# Miscellaneous.net
KiCad netlist of a schematic drawn in Altium Designer
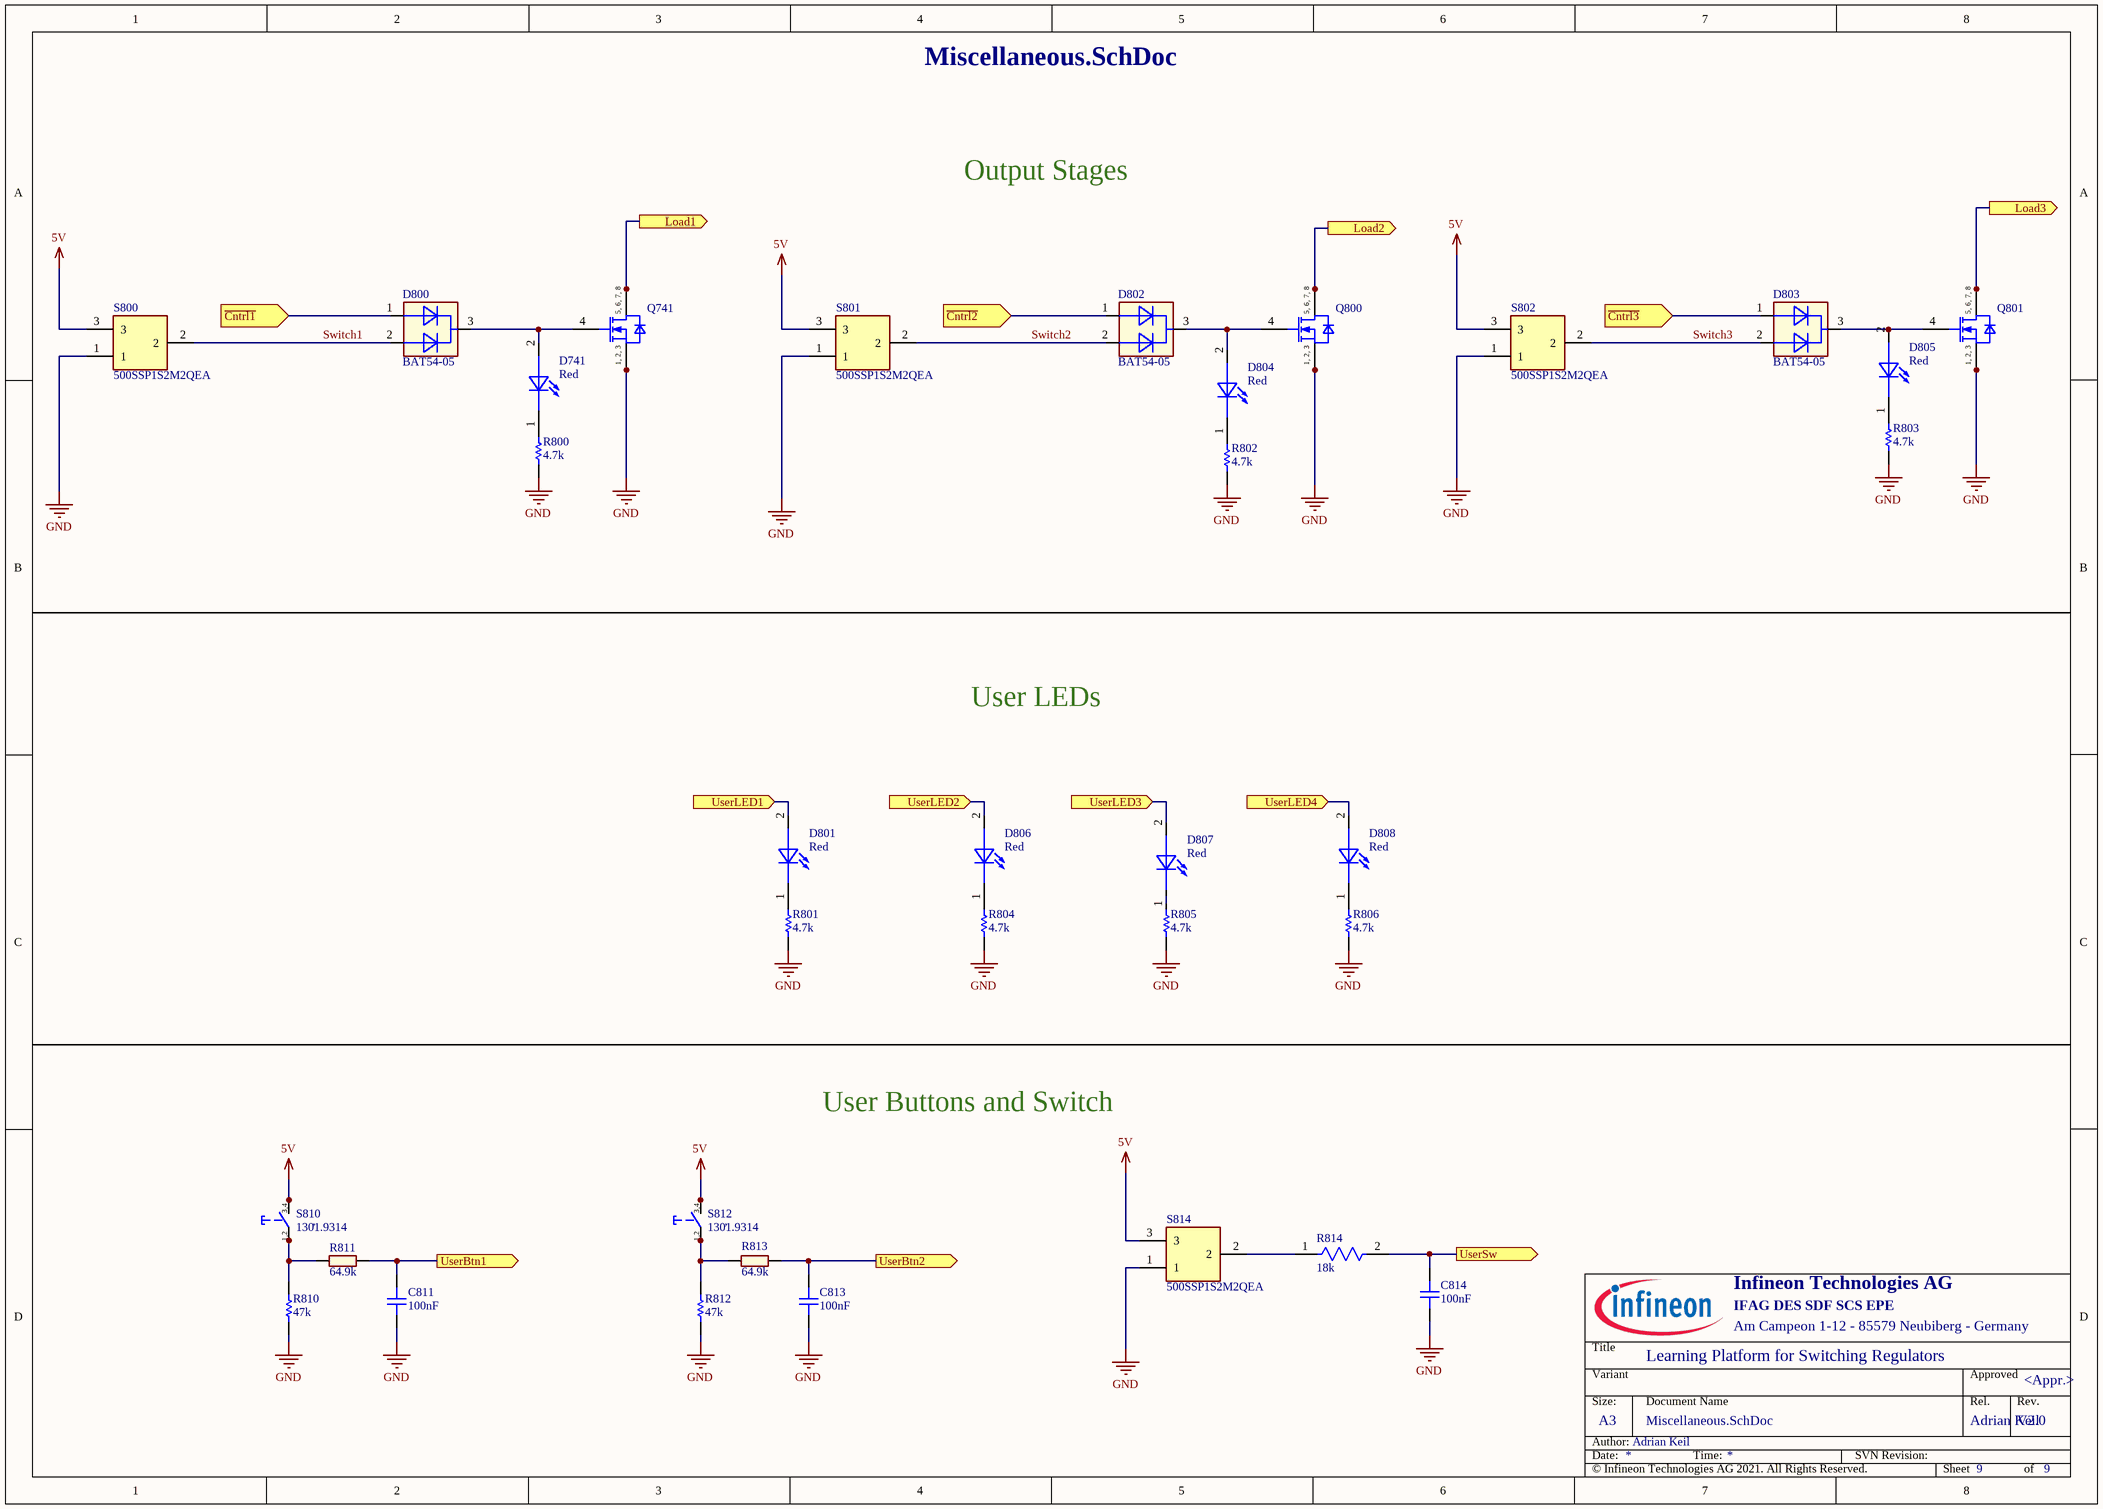
[diagram p0: Miscellaneous.SchDoc]

(export (version "E")
  (design (tool "Eeschema 10.0.6"))
  (components
    (comp (ref "C811")
      (value "100nF")
      (footprint "CAPC3216X125N-0")
      (description "CAP / CERA / 100nF / 50V / 10% / X7R (EIA) / -55°C to 125°C / 1206(3216) / SMD / -")
      (fields (field (name "LEGACY PARTNUMBER") "CAP01005660") (field (name "MANUFACTURER") "MuRata"))
      (libsource (lib "PCBLibraryData") (part "CAP-SGL-STD-02P_00000001"))
    )
    (comp (ref "C813")
      (value "100nF")
      (footprint "CAPC3216X125N-0")
      (description "CAP / CERA / 100nF / 50V / 10% / X7R (EIA) / -55°C to 125°C / 1206(3216) / SMD / -")
      (fields (field (name "LEGACY PARTNUMBER") "CAP01005660") (field (name "MANUFACTURER") "MuRata"))
      (libsource (lib "PCBLibraryData") (part "CAP-SGL-STD-02P_00000001"))
    )
    (comp (ref "C814")
      (value "100nF")
      (footprint "CAPC3216X125N-0")
      (description "CAP / CERA / 100nF / 50V / 10% / X7R (EIA) / -55°C to 125°C / 1206(3216) / SMD / -")
      (fields (field (name "LEGACY PARTNUMBER") "CAP01005660") (field (name "MANUFACTURER") "MuRata"))
      (libsource (lib "PCBLibraryData") (part "CAP-SGL-STD-02P_00000001"))
    )
    (comp (ref "D741")
      (value "Red")
      (footprint "LEDSC160X80X80-2N-1")
      (description "WL-SMCW SMT Mono-color Chip LED Waterclear, Red,630nm")
      (fields (field (name "MANUFACTURER") "Wurth Elektronik"))
      (libsource (lib "PCBLibraryData") (part "d_led_a"))
    )
    (comp (ref "D800")
      (value "BAT54-05")
      (footprint "SOT95P240X110-3N-1-V")
      (description "Silicon Schottky Diode, LS(nH) 1.8, VR 30V")
      (fields
        (field (name "LEGACY PARTNUMBER") "IFX01401370")
        (field (name "MANUFACTURER") "Infineon Technologies")
      )
      (libsource (lib "PCBLibraryData") (part "d_dual_a1a2c3_3p"))
    )
    (comp (ref "D801")
      (value "Red")
      (footprint "LEDSC160X80X80-2N-1")
      (description "WL-SMCW SMT Mono-color Chip LED Waterclear, Red,630nm")
      (fields (field (name "MANUFACTURER") "Wurth Elektronik"))
      (libsource (lib "PCBLibraryData") (part "d_led_a"))
    )
    (comp (ref "D802")
      (value "BAT54-05")
      (footprint "SOT95P240X110-3N-1-V")
      (description "Silicon Schottky Diode, LS(nH) 1.8, VR 30V")
      (fields
        (field (name "LEGACY PARTNUMBER") "IFX01401370")
        (field (name "MANUFACTURER") "Infineon Technologies")
      )
      (libsource (lib "PCBLibraryData") (part "d_dual_a1a2c3_3p"))
    )
    (comp (ref "D803")
      (value "BAT54-05")
      (footprint "SOT95P240X110-3N-1-V")
      (description "Silicon Schottky Diode, LS(nH) 1.8, VR 30V")
      (fields
        (field (name "LEGACY PARTNUMBER") "IFX01401370")
        (field (name "MANUFACTURER") "Infineon Technologies")
      )
      (libsource (lib "PCBLibraryData") (part "d_dual_a1a2c3_3p"))
    )
    (comp (ref "D804")
      (value "Red")
      (footprint "LEDSC160X80X80-2N-1")
      (description "WL-SMCW SMT Mono-color Chip LED Waterclear, Red,630nm")
      (fields (field (name "MANUFACTURER") "Wurth Elektronik"))
      (libsource (lib "PCBLibraryData") (part "d_led_a"))
    )
    (comp (ref "D805")
      (value "Red")
      (footprint "LEDSC160X80X80-2N-1")
      (description "WL-SMCW SMT Mono-color Chip LED Waterclear, Red,630nm")
      (fields (field (name "MANUFACTURER") "Wurth Elektronik"))
      (libsource (lib "PCBLibraryData") (part "d_led_a"))
    )
    (comp (ref "D806")
      (value "Red")
      (footprint "LEDSC160X80X80-2N-1")
      (description "WL-SMCW SMT Mono-color Chip LED Waterclear, Red,630nm")
      (fields (field (name "MANUFACTURER") "Wurth Elektronik"))
      (libsource (lib "PCBLibraryData") (part "d_led_a"))
    )
    (comp (ref "D807")
      (value "Red")
      (footprint "LEDSC160X80X80-2N-1")
      (description "WL-SMCW SMT Mono-color Chip LED Waterclear, Red,630nm")
      (fields (field (name "MANUFACTURER") "Wurth Elektronik"))
      (libsource (lib "PCBLibraryData") (part "d_led_a"))
    )
    (comp (ref "D808")
      (value "Red")
      (footprint "LEDSC160X80X80-2N-1")
      (description "WL-SMCW SMT Mono-color Chip LED Waterclear, Red,630nm")
      (fields (field (name "MANUFACTURER") "Wurth Elektronik"))
      (libsource (lib "PCBLibraryData") (part "d_led_a"))
    )
    (comp (ref "Q741")
      (value "igfet_n_ch_enh_dio_1s2s3s4g5d6d7d8d_8p")
      (footprint "IFX-PG-TDSON-8-6-V")
      (description "OptiMOS Power MOSFET, 30V")
      (fields (field (name "MANUFACTURER") "Infineon Technologies") (field (name "MPN") "BSC0906NSATMA1"))
      (libsource (lib "PCBLibraryData") (part "igfet_n_ch_enh_dio_1s2s3s4g5d6d7d8d_8p"))
    )
    (comp (ref "Q800")
      (value "igfet_n_ch_enh_dio_1s2s3s4g5d6d7d8d_8p")
      (footprint "IFX-PG-TDSON-8-6-V")
      (description "OptiMOS Power MOSFET, 30V")
      (fields (field (name "MANUFACTURER") "Infineon Technologies"))
      (libsource (lib "PCBLibraryData") (part "igfet_n_ch_enh_dio_1s2s3s4g5d6d7d8d_8p"))
    )
    (comp (ref "Q801")
      (value "igfet_n_ch_enh_dio_1s2s3s4g5d6d7d8d_8p")
      (footprint "IFX-PG-TDSON-8-6-V")
      (description "OptiMOS Power MOSFET, 30V")
      (fields (field (name "MANUFACTURER") "Infineon Technologies"))
      (libsource (lib "PCBLibraryData") (part "igfet_n_ch_enh_dio_1s2s3s4g5d6d7d8d_8p"))
    )
    (comp (ref "R800")
      (value "4.7k")
      (footprint "RESC3216X60X45ML15T20")
      (description "Chip Resistor, 4.7 KOhm, +/- 1%, 0.25 W, -55 to 155 degC, 1206 (3216 Metric), RoHS, Tape and Reel")
      (fields (field (name "MANUFACTURER") "Vishay Semiconductor") (field (name "TOLERANCE") "1%"))
      (libsource (lib "Altium Content Vault") (part "RES-2"))
    )
    (comp (ref "R801")
      (value "4.7k")
      (footprint "RESC3216X60X45ML15T20")
      (description "Chip Resistor, 4.7 KOhm, +/- 1%, 0.25 W, -55 to 155 degC, 1206 (3216 Metric), RoHS, Tape and Reel")
      (fields (field (name "MANUFACTURER") "Vishay Semiconductor") (field (name "TOLERANCE") "1%"))
      (libsource (lib "Altium Content Vault") (part "RES-2"))
    )
    (comp (ref "R802")
      (value "4.7k")
      (footprint "RESC3216X60X45ML15T20")
      (description "Chip Resistor, 4.7 KOhm, +/- 1%, 0.25 W, -55 to 155 degC, 1206 (3216 Metric), RoHS, Tape and Reel")
      (fields (field (name "MANUFACTURER") "Vishay Semiconductor") (field (name "TOLERANCE") "1%"))
      (libsource (lib "Altium Content Vault") (part "RES-2"))
    )
    (comp (ref "R803")
      (value "4.7k")
      (footprint "RESC3216X60X45ML15T20")
      (description "Chip Resistor, 4.7 KOhm, +/- 1%, 0.25 W, -55 to 155 degC, 1206 (3216 Metric), RoHS, Tape and Reel")
      (fields (field (name "MANUFACTURER") "Vishay Semiconductor") (field (name "TOLERANCE") "1%"))
      (libsource (lib "Altium Content Vault") (part "RES-2"))
    )
    (comp (ref "R804")
      (value "4.7k")
      (footprint "RESC3216X60X45ML15T20")
      (description "Chip Resistor, 4.7 KOhm, +/- 1%, 0.25 W, -55 to 155 degC, 1206 (3216 Metric), RoHS, Tape and Reel")
      (fields (field (name "MANUFACTURER") "Vishay Semiconductor") (field (name "TOLERANCE") "1%"))
      (libsource (lib "Altium Content Vault") (part "RES-2"))
    )
    (comp (ref "R805")
      (value "4.7k")
      (footprint "RESC3216X60X45ML15T20")
      (description "Chip Resistor, 4.7 KOhm, +/- 1%, 0.25 W, -55 to 155 degC, 1206 (3216 Metric), RoHS, Tape and Reel")
      (fields (field (name "MANUFACTURER") "Vishay Semiconductor") (field (name "TOLERANCE") "1%"))
      (libsource (lib "Altium Content Vault") (part "RES-2"))
    )
    (comp (ref "R806")
      (value "4.7k")
      (footprint "RESC3216X60X45ML15T20")
      (description "Chip Resistor, 4.7 KOhm, +/- 1%, 0.25 W, -55 to 155 degC, 1206 (3216 Metric), RoHS, Tape and Reel")
      (fields (field (name "MANUFACTURER") "Vishay Semiconductor") (field (name "TOLERANCE") "1%"))
      (libsource (lib "Altium Content Vault") (part "RES-2"))
    )
    (comp (ref "R810")
      (value "47k")
      (footprint "RESC3216X60X45LL10T20")
      (fields (field (name "PART NUMBER") "CRCW120647K0FKEA") (field (name "MANUFACTURER") "Vishay Dale"))
      (libsource (lib "Altium Content Vault") (part "RES"))
    )
    (comp (ref "R811")
      (value "64.9k")
      (footprint "RESC3216X60N")
      (description "RES / STD / 64.9k / 250mW / 1% / 100ppm/K / -55°C to 155°C / 1206(3216) / SMD / -")
      (fields (field (name "LEGACY PARTNUMBER") "RES01802950") (field (name "MANUFACTURER") "Vishay"))
      (libsource (lib "PCBLibraryData") (part "RES-SGL-STD-02P_00000006"))
    )
    (comp (ref "R812")
      (value "47k")
      (footprint "RESC3216X60X45LL10T20")
      (fields (field (name "PART NUMBER") "CRCW120647K0FKEA") (field (name "MANUFACTURER") "Vishay Dale"))
      (libsource (lib "Altium Content Vault") (part "RES"))
    )
    (comp (ref "R813")
      (value "64.9k")
      (footprint "RESC3216X60N")
      (description "RES / STD / 64.9k / 250mW / 1% / 100ppm/K / -55°C to 155°C / 1206(3216) / SMD / -")
      (fields (field (name "LEGACY PARTNUMBER") "RES01802950") (field (name "MANUFACTURER") "Vishay"))
      (libsource (lib "PCBLibraryData") (part "RES-SGL-STD-02P_00000006"))
    )
    (comp (ref "R814")
      (value "18k")
      (footprint "FP-CRCW1206-e3-IPC_C")
      (description "RES Thick Film, 18kΩ, 1%, 0.25W, 100ppm/°C, 1206")
      (fields (field (name "TOLERANCE") "1%"))
      (libsource (lib "Altium Content Vault") (part "1029c3af85768c4190bb7ad29bc67b5"))
    )
    (comp (ref "S800")
      (value "500SSP1S2M2QEA")
      (footprint "500SSP1S2M2QEA")
      (description "Connector")
      (fields (field (name "MOUSER PART NUMBER") "612-500SSP1S2M2QEA"))
      (libsource (lib "mySchlib") (part "500SSP1S2M2QEA"))
    )
    (comp (ref "S801")
      (value "500SSP1S2M2QEA")
      (footprint "500SSP1S2M2QEA")
      (description "Connector")
      (fields (field (name "MOUSER PART NUMBER") "612-500SSP1S2M2QEA"))
      (libsource (lib "mySchlib") (part "500SSP1S2M2QEA"))
    )
    (comp (ref "S802")
      (value "500SSP1S2M2QEA")
      (footprint "500SSP1S2M2QEA")
      (description "Connector")
      (fields (field (name "MOUSER PART NUMBER") "612-500SSP1S2M2QEA"))
      (libsource (lib "mySchlib") (part "500SSP1S2M2QEA"))
    )
    (comp (ref "S810")
      (value "1301.9314")
      (footprint "SW-SMD-1301.9314")
      (description "Pushbutton Tactile Switch, Single Pole Single Throw, 4 Pins")
      (fields (field (name "LEGACY PARTNUMBER") "CON01500305") (field (name "MANUFACTURER") "Schurter"))
      (libsource (lib "PCBLibraryData") (part "sw_sr_no12_34_4p"))
    )
    (comp (ref "S812")
      (value "1301.9314")
      (footprint "SW-SMD-1301.9314")
      (description "Pushbutton Tactile Switch, Single Pole Single Throw, 4 Pins")
      (fields (field (name "LEGACY PARTNUMBER") "CON01500305") (field (name "MANUFACTURER") "Schurter"))
      (libsource (lib "PCBLibraryData") (part "sw_sr_no12_34_4p"))
    )
    (comp (ref "S814")
      (value "500SSP1S2M2QEA")
      (footprint "500SSP1S2M2QEA")
      (description "Connector")
      (fields (field (name "MOUSER PART NUMBER") "612-500SSP1S2M2QEA"))
      (libsource (lib "mySchlib") (part "500SSP1S2M2QEA"))
    )
  )
  (nets
    (net (code "1") (name "/Cntrl1") (class "Default")
      (node (ref "D800") (pin "1") (pinfunction "ANODE_1_1") (pintype "passive"))
    )
    (net (code "2") (name "/Cntrl2") (class "Default")
      (node (ref "D802") (pin "1") (pinfunction "ANODE_1_1") (pintype "passive"))
    )
    (net (code "3") (name "/Cntrl3") (class "Default")
      (node (ref "D803") (pin "1") (pinfunction "ANODE_1_1") (pintype "passive"))
    )
    (net (code "4") (name "/Load1") (class "Default")
      (node (ref "Q741") (pin "5") (pinfunction "DRAIN_5") (pintype "passive"))
      (node (ref "Q741") (pin "6") (pinfunction "DRAIN_6") (pintype "passive"))
      (node (ref "Q741") (pin "7") (pinfunction "DRAIN_7") (pintype "passive"))
      (node (ref "Q741") (pin "8") (pinfunction "DRAIN_8") (pintype "passive"))
    )
    (net (code "5") (name "/Load2") (class "Default")
      (node (ref "Q800") (pin "5") (pinfunction "DRAIN_5") (pintype "passive"))
      (node (ref "Q800") (pin "6") (pinfunction "DRAIN_6") (pintype "passive"))
      (node (ref "Q800") (pin "7") (pinfunction "DRAIN_7") (pintype "passive"))
      (node (ref "Q800") (pin "8") (pinfunction "DRAIN_8") (pintype "passive"))
    )
    (net (code "6") (name "/Load3") (class "Default")
      (node (ref "Q801") (pin "5") (pinfunction "DRAIN_5") (pintype "passive"))
      (node (ref "Q801") (pin "6") (pinfunction "DRAIN_6") (pintype "passive"))
      (node (ref "Q801") (pin "7") (pinfunction "DRAIN_7") (pintype "passive"))
      (node (ref "Q801") (pin "8") (pinfunction "DRAIN_8") (pintype "passive"))
    )
    (net (code "7") (name "/Switch1") (class "Default")
      (node (ref "D800") (pin "2") (pinfunction "ANODE_2_2") (pintype "passive"))
      (node (ref "S800") (pin "2") (pinfunction "2_2") (pintype "passive"))
    )
    (net (code "8") (name "/Switch2") (class "Default")
      (node (ref "D802") (pin "2") (pinfunction "ANODE_2_2") (pintype "passive"))
      (node (ref "S801") (pin "2") (pinfunction "2_2") (pintype "passive"))
    )
    (net (code "9") (name "/Switch3") (class "Default")
      (node (ref "D803") (pin "2") (pinfunction "ANODE_2_2") (pintype "passive"))
      (node (ref "S802") (pin "2") (pinfunction "2_2") (pintype "passive"))
    )
    (net (code "10") (name "/UserBtn1") (class "Default")
      (node (ref "C811") (pin "2") (pinfunction "2_2") (pintype "passive"))
      (node (ref "R811") (pin "2") (pinfunction "2_2") (pintype "passive"))
    )
    (net (code "11") (name "/UserBtn2") (class "Default")
      (node (ref "C813") (pin "2") (pinfunction "2_2") (pintype "passive"))
      (node (ref "R813") (pin "2") (pinfunction "2_2") (pintype "passive"))
    )
    (net (code "12") (name "/UserLED1") (class "Default")
      (node (ref "D801") (pin "2") (pinfunction "Anode_2") (pintype "passive"))
    )
    (net (code "13") (name "/UserLED2") (class "Default")
      (node (ref "D806") (pin "2") (pinfunction "Anode_2") (pintype "passive"))
    )
    (net (code "14") (name "/UserLED3") (class "Default")
      (node (ref "D807") (pin "2") (pinfunction "Anode_2") (pintype "passive"))
    )
    (net (code "15") (name "/UserLED4") (class "Default")
      (node (ref "D808") (pin "2") (pinfunction "Anode_2") (pintype "passive"))
    )
    (net (code "16") (name "/UserSw") (class "Default")
      (node (ref "C814") (pin "2") (pinfunction "2_2") (pintype "passive"))
      (node (ref "R814") (pin "2") (pinfunction "2_2") (pintype "passive"))
    )
    (net (code "17") (name "5V") (class "Default")
      (node (ref "S800") (pin "3") (pinfunction "3_3") (pintype "passive"))
      (node (ref "S801") (pin "3") (pinfunction "3_3") (pintype "passive"))
      (node (ref "S802") (pin "3") (pinfunction "3_3") (pintype "passive"))
      (node (ref "S810") (pin "3") (pinfunction "3_3") (pintype "passive"))
      (node (ref "S810") (pin "4") (pinfunction "4_4") (pintype "passive"))
      (node (ref "S812") (pin "3") (pinfunction "3_3") (pintype "passive"))
      (node (ref "S812") (pin "4") (pinfunction "4_4") (pintype "passive"))
      (node (ref "S814") (pin "3") (pinfunction "3_3") (pintype "passive"))
    )
    (net (code "18") (name "GND") (class "Default")
      (node (ref "C811") (pin "1") (pinfunction "1_1") (pintype "passive"))
      (node (ref "C813") (pin "1") (pinfunction "1_1") (pintype "passive"))
      (node (ref "C814") (pin "1") (pinfunction "1_1") (pintype "passive"))
      (node (ref "Q741") (pin "1") (pinfunction "SOURCE_1") (pintype "passive"))
      (node (ref "Q741") (pin "2") (pinfunction "SOURCE_2") (pintype "passive"))
      (node (ref "Q741") (pin "3") (pinfunction "SOURCE_3") (pintype "passive"))
      (node (ref "Q800") (pin "1") (pinfunction "SOURCE_1") (pintype "passive"))
      (node (ref "Q800") (pin "2") (pinfunction "SOURCE_2") (pintype "passive"))
      (node (ref "Q800") (pin "3") (pinfunction "SOURCE_3") (pintype "passive"))
      (node (ref "Q801") (pin "1") (pinfunction "SOURCE_1") (pintype "passive"))
      (node (ref "Q801") (pin "2") (pinfunction "SOURCE_2") (pintype "passive"))
      (node (ref "Q801") (pin "3") (pinfunction "SOURCE_3") (pintype "passive"))
      (node (ref "R800") (pin "1") (pinfunction "1_1") (pintype "passive"))
      (node (ref "R801") (pin "1") (pinfunction "1_1") (pintype "passive"))
      (node (ref "R802") (pin "1") (pinfunction "1_1") (pintype "passive"))
      (node (ref "R803") (pin "1") (pinfunction "1_1") (pintype "passive"))
      (node (ref "R804") (pin "1") (pinfunction "1_1") (pintype "passive"))
      (node (ref "R805") (pin "1") (pinfunction "1_1") (pintype "passive"))
      (node (ref "R806") (pin "1") (pinfunction "1_1") (pintype "passive"))
      (node (ref "R810") (pin "1") (pinfunction "1_1") (pintype "passive"))
      (node (ref "R812") (pin "1") (pinfunction "1_1") (pintype "passive"))
      (node (ref "S800") (pin "1") (pinfunction "1_1") (pintype "passive"))
      (node (ref "S801") (pin "1") (pinfunction "1_1") (pintype "passive"))
      (node (ref "S802") (pin "1") (pinfunction "1_1") (pintype "passive"))
      (node (ref "S814") (pin "1") (pinfunction "1_1") (pintype "passive"))
    )
    (net (code "19") (name "Net-(D741-Anode)") (class "Default")
      (node (ref "D741") (pin "2") (pinfunction "Anode_2") (pintype "passive"))
      (node (ref "D800") (pin "3") (pinfunction "CATHODE_3") (pintype "passive"))
      (node (ref "Q741") (pin "4") (pinfunction "GATE_4") (pintype "passive"))
    )
    (net (code "20") (name "Net-(D741-Cathode)") (class "Default")
      (node (ref "D741") (pin "1") (pinfunction "Cathode_1") (pintype "passive"))
      (node (ref "R800") (pin "2") (pinfunction "2_2") (pintype "passive"))
    )
    (net (code "21") (name "Net-(D801-Cathode)") (class "Default")
      (node (ref "D801") (pin "1") (pinfunction "Cathode_1") (pintype "passive"))
      (node (ref "R801") (pin "2") (pinfunction "2_2") (pintype "passive"))
    )
    (net (code "22") (name "Net-(D802-CATHODE)") (class "Default")
      (node (ref "D802") (pin "3") (pinfunction "CATHODE_3") (pintype "passive"))
      (node (ref "D804") (pin "2") (pinfunction "Anode_2") (pintype "passive"))
      (node (ref "Q800") (pin "4") (pinfunction "GATE_4") (pintype "passive"))
    )
    (net (code "23") (name "Net-(D803-CATHODE)") (class "Default")
      (node (ref "D803") (pin "3") (pinfunction "CATHODE_3") (pintype "passive"))
      (node (ref "D805") (pin "2") (pinfunction "Anode_2") (pintype "passive"))
      (node (ref "Q801") (pin "4") (pinfunction "GATE_4") (pintype "passive"))
    )
    (net (code "24") (name "Net-(D804-Cathode)") (class "Default")
      (node (ref "D804") (pin "1") (pinfunction "Cathode_1") (pintype "passive"))
      (node (ref "R802") (pin "2") (pinfunction "2_2") (pintype "passive"))
    )
    (net (code "25") (name "Net-(D805-Cathode)") (class "Default")
      (node (ref "D805") (pin "1") (pinfunction "Cathode_1") (pintype "passive"))
      (node (ref "R803") (pin "2") (pinfunction "2_2") (pintype "passive"))
    )
    (net (code "26") (name "Net-(D806-Cathode)") (class "Default")
      (node (ref "D806") (pin "1") (pinfunction "Cathode_1") (pintype "passive"))
      (node (ref "R804") (pin "2") (pinfunction "2_2") (pintype "passive"))
    )
    (net (code "27") (name "Net-(D807-Cathode)") (class "Default")
      (node (ref "D807") (pin "1") (pinfunction "Cathode_1") (pintype "passive"))
      (node (ref "R805") (pin "2") (pinfunction "2_2") (pintype "passive"))
    )
    (net (code "28") (name "Net-(D808-Cathode)") (class "Default")
      (node (ref "D808") (pin "1") (pinfunction "Cathode_1") (pintype "passive"))
      (node (ref "R806") (pin "2") (pinfunction "2_2") (pintype "passive"))
    )
    (net (code "29") (name "Net-(R810-Pad2)") (class "Default")
      (node (ref "R810") (pin "2") (pinfunction "2_2") (pintype "passive"))
      (node (ref "R811") (pin "1") (pinfunction "1_1") (pintype "passive"))
      (node (ref "S810") (pin "1") (pinfunction "1_1") (pintype "passive"))
      (node (ref "S810") (pin "2") (pinfunction "2_2") (pintype "passive"))
    )
    (net (code "30") (name "Net-(R812-Pad2)") (class "Default")
      (node (ref "R812") (pin "2") (pinfunction "2_2") (pintype "passive"))
      (node (ref "R813") (pin "1") (pinfunction "1_1") (pintype "passive"))
      (node (ref "S812") (pin "1") (pinfunction "1_1") (pintype "passive"))
      (node (ref "S812") (pin "2") (pinfunction "2_2") (pintype "passive"))
    )
    (net (code "31") (name "Net-(R814-Pad1)") (class "Default")
      (node (ref "R814") (pin "1") (pinfunction "1_1") (pintype "passive"))
      (node (ref "S814") (pin "2") (pinfunction "2_2") (pintype "passive"))
    )
  )
)
